# voltage_sensor_v0_4.net
KiCad netlist of a schematic drawn in EAGLE
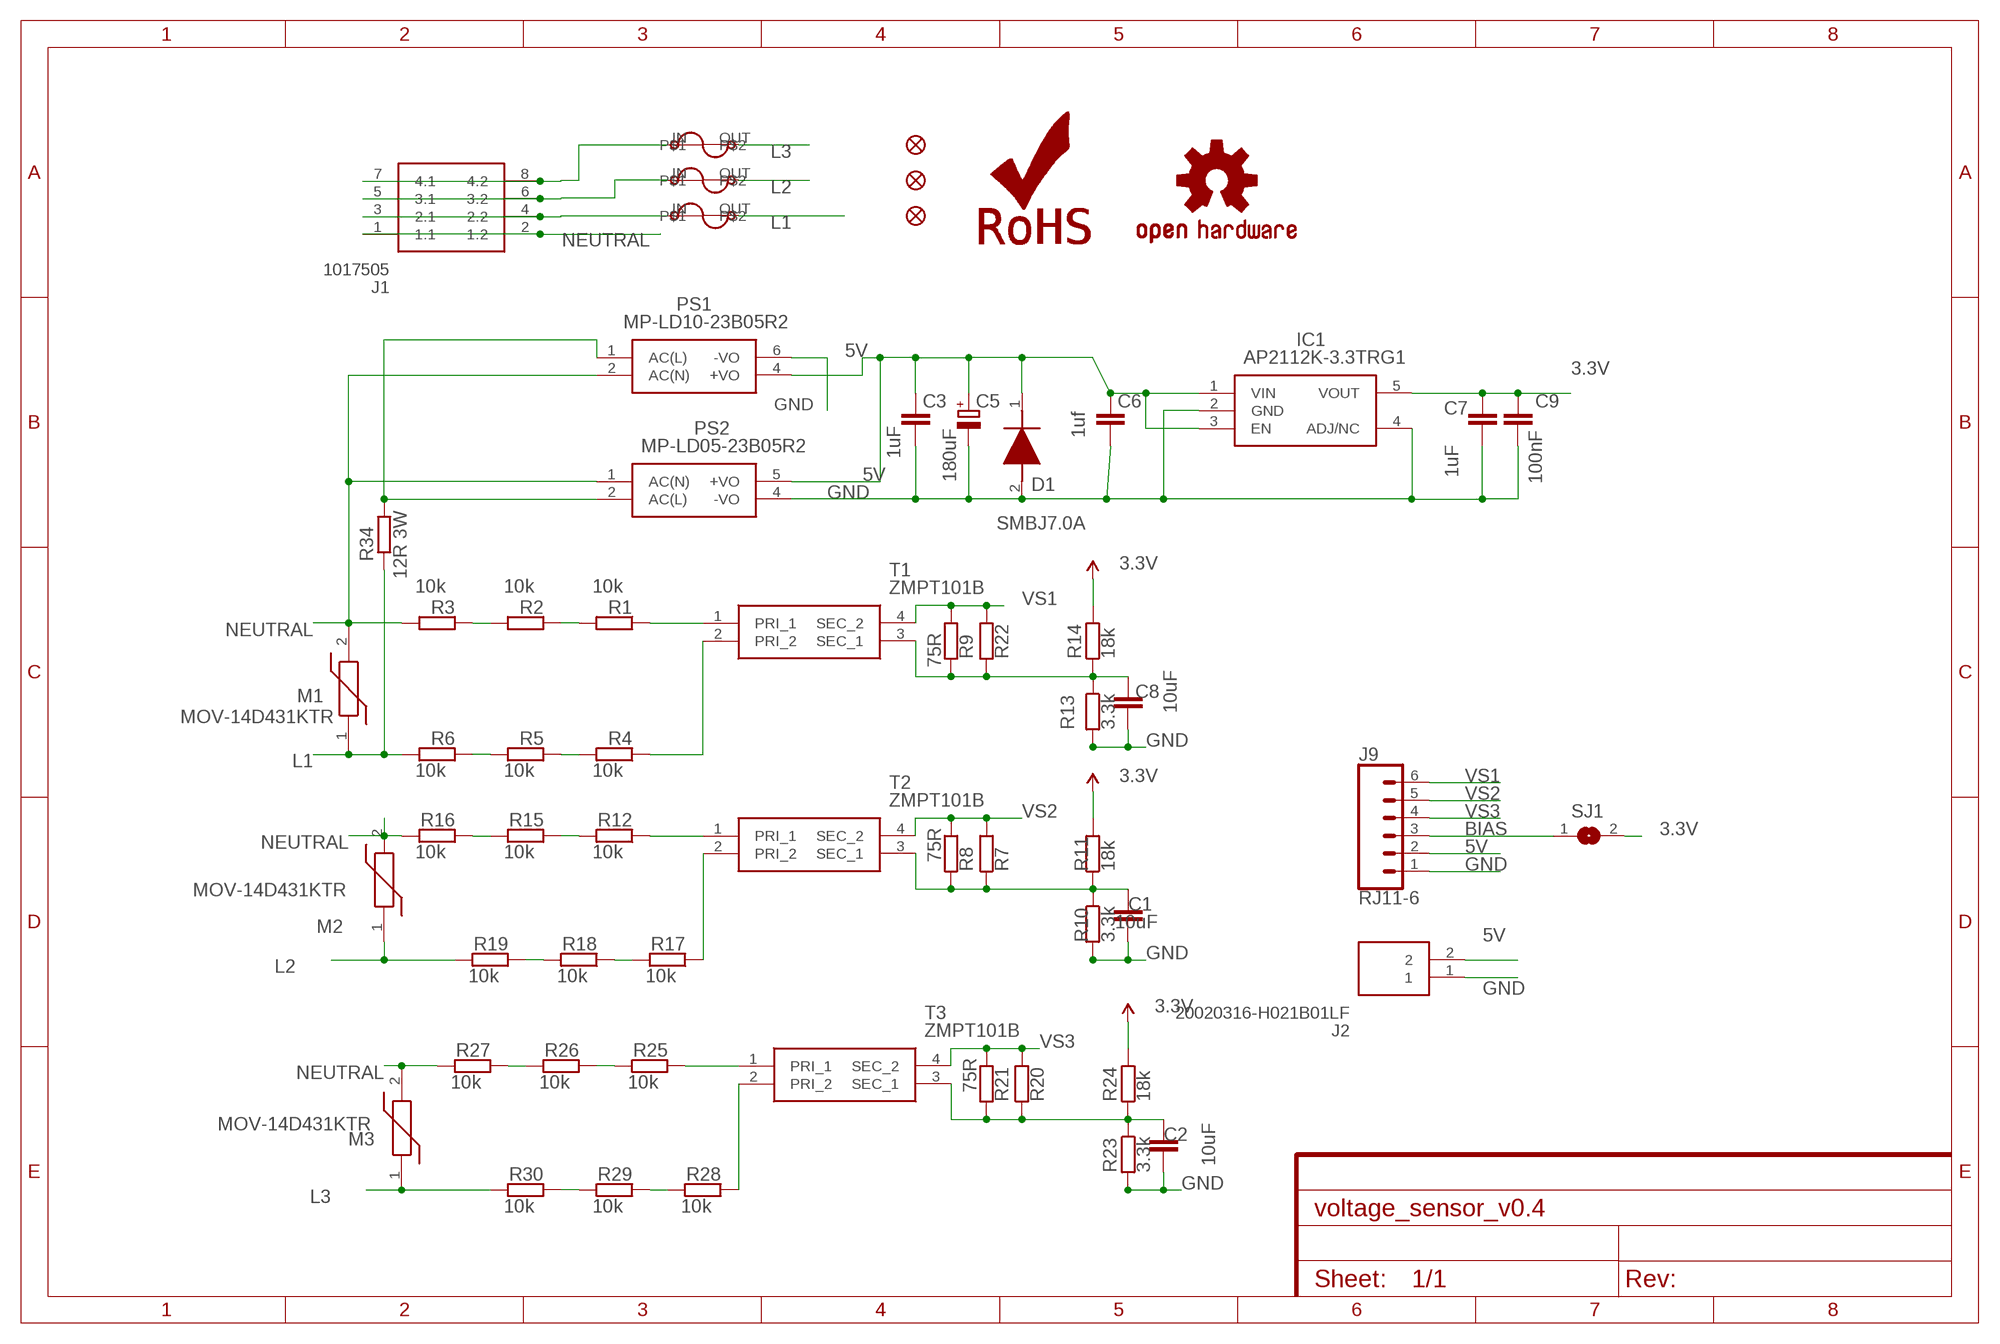
[diagram p0: schematic, sheet 1]

(export (version "E")
  (design (tool "Eeschema 10.0.6"))
  (components
    (comp (ref "C1")
      (value "10uF")
      (footprint "eagle-import:C0603")
      (libsource (lib "eagle-import") (part "C-EUC0603"))
    )
    (comp (ref "C2")
      (value "10uF")
      (footprint "eagle-import:C0603")
      (libsource (lib "eagle-import") (part "C-EUC0603"))
    )
    (comp (ref "C3")
      (value "1uF")
      (footprint "eagle-import:C0603")
      (libsource (lib "eagle-import") (part "C-EUC0603"))
    )
    (comp (ref "C5")
      (value "180uF")
      (footprint "eagle-import:PANASONIC_C")
      (libsource (lib "eagle-import") (part "CPOL-EUC"))
    )
    (comp (ref "C6")
      (value "1uf")
      (footprint "eagle-import:C0603")
      (libsource (lib "eagle-import") (part "C-EUC0603"))
    )
    (comp (ref "C7")
      (value "1uF")
      (footprint "eagle-import:C0603")
      (libsource (lib "eagle-import") (part "C-EUC0603"))
    )
    (comp (ref "C8")
      (value "10uF")
      (footprint "eagle-import:C0603")
      (libsource (lib "eagle-import") (part "C-EUC0603"))
    )
    (comp (ref "C9")
      (value "100nF")
      (footprint "eagle-import:C0603")
      (libsource (lib "eagle-import") (part "C-EUC0603"))
    )
    (comp (ref "D1")
      (value "SMBJ7.0A")
      (footprint "eagle-import:DIOM5336X244N")
      (libsource (lib "eagle-import") (part "SMBJ7.0A"))
    )
    (comp (ref "F1")
      (value "2A/250V")
      (footprint "eagle-import:BELFUSE1A")
      (libsource (lib "eagle-import") (part "BEL1AFUSE"))
    )
    (comp (ref "F2")
      (value "2A/250V")
      (footprint "eagle-import:BELFUSE1A")
      (libsource (lib "eagle-import") (part "BEL1AFUSE"))
    )
    (comp (ref "F3")
      (value "2A/250V")
      (footprint "eagle-import:BELFUSE1A")
      (libsource (lib "eagle-import") (part "BEL1AFUSE"))
    )
    (comp (ref "FD1")
      (value "FIDUCIAL1X2")
      (footprint "eagle-import:FIDUCIAL-1X2")
      (libsource (lib "eagle-import") (part "FIDUCIAL1X2"))
    )
    (comp (ref "FD2")
      (value "FIDUCIAL1X2")
      (footprint "eagle-import:FIDUCIAL-1X2")
      (libsource (lib "eagle-import") (part "FIDUCIAL1X2"))
    )
    (comp (ref "FD3")
      (value "FIDUCIAL1X2")
      (footprint "eagle-import:FIDUCIAL-1X2")
      (libsource (lib "eagle-import") (part "FIDUCIAL1X2"))
    )
    (comp (ref "IC1")
      (value "AP2112K-3.3TRG1")
      (footprint "eagle-import:SOT95P282X130-5N")
      (fields (field (name "MOUSER_PART_NUMBER") "621-AP2112K-3.3TRG1"))
      (libsource (lib "eagle-import") (part "AP2112K-3.3TRG1"))
    )
    (comp (ref "J1")
      (value "1017505")
      (footprint "eagle-import:1017505")
      (fields (field (name "MOUSER_PART_NUMBER") "651-1017505"))
      (libsource (lib "eagle-import") (part "1017505"))
    )
    (comp (ref "J2")
      (value "20020316-H021B01LF")
      (footprint "eagle-import:20020316H021B01LF")
      (libsource (lib "eagle-import") (part "20020316-H021B01LF"))
    )
    (comp (ref "J9")
      (value "RJ11-6")
      (footprint "eagle-import:RJ11-6")
      (libsource (lib "eagle-import") (part "RJ11-6"))
    )
    (comp (ref "LOGO1")
      (value "ROHS_LOGO")
      (footprint "eagle-import:ROHS_LOGO_0.18_IN")
      (libsource (lib "eagle-import") (part "ROHS_LOGO"))
    )
    (comp (ref "LOGO2")
      (value "OSHW-LOGOS-COPPER")
      (footprint "eagle-import:OSHW-LOGO-S_COPPER")
      (libsource (lib "eagle-import") (part "OSHW-LOGOS-COPPER"))
    )
    (comp (ref "M1")
      (value "MOV-14D431KTR")
      (footprint "eagle-import:MOV14D431KTR")
      (fields (field (name "MOUSER_PART_NUMBER") "652-MOV-14D431KTR"))
      (libsource (lib "eagle-import") (part "MOV-14D431KTR"))
    )
    (comp (ref "M2")
      (value "MOV-14D431KTR")
      (footprint "eagle-import:MOV14D431KTR")
      (fields (field (name "MOUSER_PART_NUMBER") "652-MOV-14D431KTR"))
      (libsource (lib "eagle-import") (part "MOV-14D431KTR"))
    )
    (comp (ref "M3")
      (value "MOV-14D431KTR")
      (footprint "eagle-import:MOV14D431KTR")
      (fields (field (name "MOUSER_PART_NUMBER") "652-MOV-14D431KTR"))
      (libsource (lib "eagle-import") (part "MOV-14D431KTR"))
    )
    (comp (ref "PS1")
      (value "MP-LD10-23B05R2")
      (footprint "eagle-import:MPLD1023B12R2")
      (libsource (lib "eagle-import") (part "MP-LD10-23B12R2"))
    )
    (comp (ref "PS2")
      (value "MP-LD05-23B05R2")
      (footprint "eagle-import:MPLD0523B03R2")
      (fields (field (name "MANUFACTURER_PART_NUMBER") "MP-LD05-23B03R2"))
      (libsource (lib "eagle-import") (part "MP-LD05-23B03R2"))
    )
    (comp (ref "R1")
      (value "10k")
      (footprint "eagle-import:R0603")
      (libsource (lib "eagle-import") (part "R-EU_R0603"))
    )
    (comp (ref "R2")
      (value "10k")
      (footprint "eagle-import:R0603")
      (libsource (lib "eagle-import") (part "R-EU_R0603"))
    )
    (comp (ref "R3")
      (value "10k")
      (footprint "eagle-import:R0603")
      (libsource (lib "eagle-import") (part "R-EU_R0603"))
    )
    (comp (ref "R4")
      (value "10k")
      (footprint "eagle-import:R0603")
      (libsource (lib "eagle-import") (part "R-EU_R0603"))
    )
    (comp (ref "R5")
      (value "10k")
      (footprint "eagle-import:R0603")
      (libsource (lib "eagle-import") (part "R-EU_R0603"))
    )
    (comp (ref "R6")
      (value "10k")
      (footprint "eagle-import:R0603")
      (libsource (lib "eagle-import") (part "R-EU_R0603"))
    )
    (comp (ref "R7")
      (value "R-EU_0204/7")
      (footprint "eagle-import:0204_7")
      (libsource (lib "eagle-import") (part "R-EU_0204/7"))
    )
    (comp (ref "R8")
      (value "75R")
      (footprint "eagle-import:R0603")
      (libsource (lib "eagle-import") (part "R-EU_R0603"))
    )
    (comp (ref "R9")
      (value "75R")
      (footprint "eagle-import:R0603")
      (libsource (lib "eagle-import") (part "R-EU_R0603"))
    )
    (comp (ref "R10")
      (value "3.3k")
      (footprint "eagle-import:R0603")
      (libsource (lib "eagle-import") (part "R-EU_R0603"))
    )
    (comp (ref "R11")
      (value "18k")
      (footprint "eagle-import:R0603")
      (libsource (lib "eagle-import") (part "R-EU_R0603"))
    )
    (comp (ref "R12")
      (value "10k")
      (footprint "eagle-import:R0603")
      (libsource (lib "eagle-import") (part "R-EU_R0603"))
    )
    (comp (ref "R13")
      (value "3.3k")
      (footprint "eagle-import:R0603")
      (libsource (lib "eagle-import") (part "R-EU_R0603"))
    )
    (comp (ref "R14")
      (value "18k")
      (footprint "eagle-import:R0603")
      (libsource (lib "eagle-import") (part "R-EU_R0603"))
    )
    (comp (ref "R15")
      (value "10k")
      (footprint "eagle-import:R0603")
      (libsource (lib "eagle-import") (part "R-EU_R0603"))
    )
    (comp (ref "R16")
      (value "10k")
      (footprint "eagle-import:R0603")
      (libsource (lib "eagle-import") (part "R-EU_R0603"))
    )
    (comp (ref "R17")
      (value "10k")
      (footprint "eagle-import:R0603")
      (libsource (lib "eagle-import") (part "R-EU_R0603"))
    )
    (comp (ref "R18")
      (value "10k")
      (footprint "eagle-import:R0603")
      (libsource (lib "eagle-import") (part "R-EU_R0603"))
    )
    (comp (ref "R19")
      (value "10k")
      (footprint "eagle-import:R0603")
      (libsource (lib "eagle-import") (part "R-EU_R0603"))
    )
    (comp (ref "R20")
      (value "R-EU_0204/7")
      (footprint "eagle-import:0204_7")
      (libsource (lib "eagle-import") (part "R-EU_0204/7"))
    )
    (comp (ref "R21")
      (value "75R")
      (footprint "eagle-import:R0603")
      (libsource (lib "eagle-import") (part "R-EU_R0603"))
    )
    (comp (ref "R22")
      (value "R-EU_0204/7")
      (footprint "eagle-import:0204_7")
      (libsource (lib "eagle-import") (part "R-EU_0204/7"))
    )
    (comp (ref "R23")
      (value "3.3k")
      (footprint "eagle-import:R0603")
      (libsource (lib "eagle-import") (part "R-EU_R0603"))
    )
    (comp (ref "R24")
      (value "18k")
      (footprint "eagle-import:R0603")
      (libsource (lib "eagle-import") (part "R-EU_R0603"))
    )
    (comp (ref "R25")
      (value "10k")
      (footprint "eagle-import:R0603")
      (libsource (lib "eagle-import") (part "R-EU_R0603"))
    )
    (comp (ref "R26")
      (value "10k")
      (footprint "eagle-import:R0603")
      (libsource (lib "eagle-import") (part "R-EU_R0603"))
    )
    (comp (ref "R27")
      (value "10k")
      (footprint "eagle-import:R0603")
      (libsource (lib "eagle-import") (part "R-EU_R0603"))
    )
    (comp (ref "R28")
      (value "10k")
      (footprint "eagle-import:R0603")
      (libsource (lib "eagle-import") (part "R-EU_R0603"))
    )
    (comp (ref "R29")
      (value "10k")
      (footprint "eagle-import:R0603")
      (libsource (lib "eagle-import") (part "R-EU_R0603"))
    )
    (comp (ref "R30")
      (value "10k")
      (footprint "eagle-import:R0603")
      (libsource (lib "eagle-import") (part "R-EU_R0603"))
    )
    (comp (ref "R34")
      (value "12R 3W")
      (footprint "eagle-import:R2512")
      (libsource (lib "eagle-import") (part "rcl_334_R-EU_R2512"))
    )
    (comp (ref "SJ1") (value "SJ") (footprint "eagle-import:SJ") (libsource (lib "eagle-import") (part "SJ")))
    (comp (ref "T1")
      (value "ZMPT101B")
      (footprint "eagle-import:ZMPT101B")
      (libsource (lib "eagle-import") (part "ZMPT101B"))
    )
    (comp (ref "T2")
      (value "ZMPT101B")
      (footprint "eagle-import:ZMPT101B")
      (libsource (lib "eagle-import") (part "ZMPT101B"))
    )
    (comp (ref "T3")
      (value "ZMPT101B")
      (footprint "eagle-import:ZMPT101B")
      (libsource (lib "eagle-import") (part "ZMPT101B"))
    )
  )
  (nets
    (net (code "1") (name "/5V") (class "Default")
      (node (ref "C3") (pin "1") (pinfunction "1_1") (pintype "passive"))
      (node (ref "C5") (pin "+") (pinfunction "+_+") (pintype "passive"))
      (node (ref "C6") (pin "1") (pinfunction "1_1") (pintype "passive"))
      (node (ref "D1") (pin "1") (pinfunction "K_1") (pintype "bidirectional"))
      (node (ref "IC1") (pin "1") (pinfunction "VIN_1") (pintype "bidirectional"))
      (node (ref "IC1") (pin "3") (pinfunction "EN_3") (pintype "bidirectional"))
      (node (ref "J2") (pin "2") (pinfunction "2_2") (pintype "bidirectional"))
      (node (ref "J9") (pin "2") (pinfunction "2_2") (pintype "passive"))
      (node (ref "PS1") (pin "4") (pinfunction "+VO_4") (pintype "bidirectional"))
      (node (ref "PS2") (pin "5") (pinfunction "+VO_5") (pintype "bidirectional"))
    )
    (net (code "2") (name "/BIAS") (class "Default")
      (node (ref "J9") (pin "3") (pinfunction "3_3") (pintype "passive"))
      (node (ref "SJ1") (pin "1") (pinfunction "1_1") (pintype "passive"))
    )
    (net (code "3") (name "/GND") (class "Default")
      (node (ref "C1") (pin "2") (pinfunction "2_2") (pintype "passive"))
      (node (ref "C2") (pin "2") (pinfunction "2_2") (pintype "passive"))
      (node (ref "C3") (pin "2") (pinfunction "2_2") (pintype "passive"))
      (node (ref "C5") (pin "-") (pinfunction "-_-") (pintype "passive"))
      (node (ref "C6") (pin "2") (pinfunction "2_2") (pintype "passive"))
      (node (ref "C7") (pin "2") (pinfunction "2_2") (pintype "passive"))
      (node (ref "C8") (pin "2") (pinfunction "2_2") (pintype "passive"))
      (node (ref "C9") (pin "2") (pinfunction "2_2") (pintype "passive"))
      (node (ref "D1") (pin "2") (pinfunction "A_2") (pintype "bidirectional"))
      (node (ref "IC1") (pin "2") (pinfunction "GND_2") (pintype "bidirectional"))
      (node (ref "IC1") (pin "4") (pinfunction "ADJ/NC_4") (pintype "bidirectional"))
      (node (ref "J2") (pin "1") (pinfunction "1_1") (pintype "bidirectional"))
      (node (ref "J9") (pin "1") (pinfunction "1_1") (pintype "passive"))
      (node (ref "PS1") (pin "6") (pinfunction "-VO_6") (pintype "bidirectional"))
      (node (ref "PS2") (pin "4") (pinfunction "-VO_4") (pintype "bidirectional"))
      (node (ref "R10") (pin "2") (pinfunction "2_2") (pintype "passive"))
      (node (ref "R13") (pin "2") (pinfunction "2_2") (pintype "passive"))
      (node (ref "R23") (pin "2") (pinfunction "2_2") (pintype "passive"))
    )
    (net (code "4") (name "/L1") (class "Default")
      (node (ref "F1") (pin "OUT") (pinfunction "P$1_OUT") (pintype "bidirectional"))
      (node (ref "M1") (pin "1") (pinfunction "1_1") (pintype "bidirectional"))
      (node (ref "R34") (pin "1") (pinfunction "1_1") (pintype "passive"))
      (node (ref "R6") (pin "2") (pinfunction "2_2") (pintype "passive"))
    )
    (net (code "5") (name "/L2") (class "Default")
      (node (ref "F2") (pin "OUT") (pinfunction "P$1_OUT") (pintype "bidirectional"))
      (node (ref "M2") (pin "1") (pinfunction "1_1") (pintype "bidirectional"))
      (node (ref "R19") (pin "2") (pinfunction "2_2") (pintype "passive"))
    )
    (net (code "6") (name "/L3") (class "Default")
      (node (ref "F3") (pin "OUT") (pinfunction "P$1_OUT") (pintype "bidirectional"))
      (node (ref "M3") (pin "1") (pinfunction "1_1") (pintype "bidirectional"))
      (node (ref "R30") (pin "2") (pinfunction "2_2") (pintype "passive"))
    )
    (net (code "7") (name "/NEUTRAL") (class "Default")
      (node (ref "J1") (pin "1") (pinfunction "1.1_1") (pintype "bidirectional"))
      (node (ref "J1") (pin "2") (pinfunction "1.2_2") (pintype "bidirectional"))
      (node (ref "M1") (pin "2") (pinfunction "2_2") (pintype "bidirectional"))
      (node (ref "M2") (pin "2") (pinfunction "2_2") (pintype "bidirectional"))
      (node (ref "M3") (pin "2") (pinfunction "2_2") (pintype "bidirectional"))
      (node (ref "PS1") (pin "2") (pinfunction "AC(N)_2") (pintype "bidirectional"))
      (node (ref "PS2") (pin "1") (pinfunction "AC(N)_1") (pintype "bidirectional"))
      (node (ref "R16") (pin "2") (pinfunction "2_2") (pintype "passive"))
      (node (ref "R27") (pin "2") (pinfunction "2_2") (pintype "passive"))
      (node (ref "R3") (pin "2") (pinfunction "2_2") (pintype "passive"))
    )
    (net (code "8") (name "/VS1") (class "Default")
      (node (ref "J9") (pin "6") (pinfunction "6_6") (pintype "passive"))
      (node (ref "R22") (pin "2") (pinfunction "2_2") (pintype "passive"))
      (node (ref "R9") (pin "2") (pinfunction "2_2") (pintype "passive"))
      (node (ref "T1") (pin "4") (pinfunction "SEC_2_4") (pintype "bidirectional"))
    )
    (net (code "9") (name "/VS2") (class "Default")
      (node (ref "J9") (pin "5") (pinfunction "5_5") (pintype "passive"))
      (node (ref "R7") (pin "2") (pinfunction "2_2") (pintype "passive"))
      (node (ref "R8") (pin "2") (pinfunction "2_2") (pintype "passive"))
      (node (ref "T2") (pin "4") (pinfunction "SEC_2_4") (pintype "bidirectional"))
    )
    (net (code "10") (name "/VS3") (class "Default")
      (node (ref "J9") (pin "4") (pinfunction "4_4") (pintype "passive"))
      (node (ref "R20") (pin "2") (pinfunction "2_2") (pintype "passive"))
      (node (ref "R21") (pin "2") (pinfunction "2_2") (pintype "passive"))
      (node (ref "T3") (pin "4") (pinfunction "SEC_2_4") (pintype "bidirectional"))
    )
    (net (code "11") (name "3.3V") (class "Default")
      (node (ref "C7") (pin "1") (pinfunction "1_1") (pintype "passive"))
      (node (ref "C9") (pin "1") (pinfunction "1_1") (pintype "passive"))
      (node (ref "IC1") (pin "5") (pinfunction "VOUT_5") (pintype "bidirectional"))
      (node (ref "R11") (pin "2") (pinfunction "2_2") (pintype "passive"))
      (node (ref "R14") (pin "2") (pinfunction "2_2") (pintype "passive"))
      (node (ref "R24") (pin "2") (pinfunction "2_2") (pintype "passive"))
      (node (ref "SJ1") (pin "2") (pinfunction "2_2") (pintype "passive"))
    )
    (net (code "12") (name "Net-(F1-P$2)") (class "Default")
      (node (ref "F1") (pin "IN") (pinfunction "P$2_IN") (pintype "bidirectional"))
      (node (ref "J1") (pin "3") (pinfunction "2.1_3") (pintype "bidirectional"))
      (node (ref "J1") (pin "4") (pinfunction "2.2_4") (pintype "bidirectional"))
    )
    (net (code "13") (name "Net-(F2-P$2)") (class "Default")
      (node (ref "F2") (pin "IN") (pinfunction "P$2_IN") (pintype "bidirectional"))
      (node (ref "J1") (pin "5") (pinfunction "3.1_5") (pintype "bidirectional"))
      (node (ref "J1") (pin "6") (pinfunction "3.2_6") (pintype "bidirectional"))
    )
    (net (code "14") (name "Net-(F3-P$2)") (class "Default")
      (node (ref "F3") (pin "IN") (pinfunction "P$2_IN") (pintype "bidirectional"))
      (node (ref "J1") (pin "7") (pinfunction "4.1_7") (pintype "bidirectional"))
      (node (ref "J1") (pin "8") (pinfunction "4.2_8") (pintype "bidirectional"))
    )
    (net (code "15") (name "Net-(PS1-AC(L))") (class "Default")
      (node (ref "PS1") (pin "1") (pinfunction "AC(L)_1") (pintype "bidirectional"))
      (node (ref "PS2") (pin "2") (pinfunction "AC(L)_2") (pintype "bidirectional"))
      (node (ref "R34") (pin "2") (pinfunction "2_2") (pintype "passive"))
    )
    (net (code "16") (name "Net-(R1-Pad2)") (class "Default")
      (node (ref "R1") (pin "2") (pinfunction "2_2") (pintype "passive"))
      (node (ref "R2") (pin "1") (pinfunction "1_1") (pintype "passive"))
    )
    (net (code "17") (name "Net-(R2-Pad2)") (class "Default")
      (node (ref "R2") (pin "2") (pinfunction "2_2") (pintype "passive"))
      (node (ref "R3") (pin "1") (pinfunction "1_1") (pintype "passive"))
    )
    (net (code "18") (name "Net-(R4-Pad2)") (class "Default")
      (node (ref "R4") (pin "2") (pinfunction "2_2") (pintype "passive"))
      (node (ref "R5") (pin "1") (pinfunction "1_1") (pintype "passive"))
    )
    (net (code "19") (name "Net-(R5-Pad2)") (class "Default")
      (node (ref "R5") (pin "2") (pinfunction "2_2") (pintype "passive"))
      (node (ref "R6") (pin "1") (pinfunction "1_1") (pintype "passive"))
    )
    (net (code "20") (name "Net-(R12-Pad2)") (class "Default")
      (node (ref "R12") (pin "2") (pinfunction "2_2") (pintype "passive"))
      (node (ref "R15") (pin "1") (pinfunction "1_1") (pintype "passive"))
    )
    (net (code "21") (name "Net-(R15-Pad2)") (class "Default")
      (node (ref "R15") (pin "2") (pinfunction "2_2") (pintype "passive"))
      (node (ref "R16") (pin "1") (pinfunction "1_1") (pintype "passive"))
    )
    (net (code "22") (name "Net-(R17-Pad2)") (class "Default")
      (node (ref "R17") (pin "2") (pinfunction "2_2") (pintype "passive"))
      (node (ref "R18") (pin "1") (pinfunction "1_1") (pintype "passive"))
    )
    (net (code "23") (name "Net-(R18-Pad2)") (class "Default")
      (node (ref "R18") (pin "2") (pinfunction "2_2") (pintype "passive"))
      (node (ref "R19") (pin "1") (pinfunction "1_1") (pintype "passive"))
    )
    (net (code "24") (name "Net-(R25-Pad2)") (class "Default")
      (node (ref "R25") (pin "2") (pinfunction "2_2") (pintype "passive"))
      (node (ref "R26") (pin "1") (pinfunction "1_1") (pintype "passive"))
    )
    (net (code "25") (name "Net-(R26-Pad2)") (class "Default")
      (node (ref "R26") (pin "2") (pinfunction "2_2") (pintype "passive"))
      (node (ref "R27") (pin "1") (pinfunction "1_1") (pintype "passive"))
    )
    (net (code "26") (name "Net-(R28-Pad2)") (class "Default")
      (node (ref "R28") (pin "2") (pinfunction "2_2") (pintype "passive"))
      (node (ref "R29") (pin "1") (pinfunction "1_1") (pintype "passive"))
    )
    (net (code "27") (name "Net-(R29-Pad2)") (class "Default")
      (node (ref "R29") (pin "2") (pinfunction "2_2") (pintype "passive"))
      (node (ref "R30") (pin "1") (pinfunction "1_1") (pintype "passive"))
    )
    (net (code "28") (name "Net-(T1-PRI_1)") (class "Default")
      (node (ref "R1") (pin "1") (pinfunction "1_1") (pintype "passive"))
      (node (ref "T1") (pin "1") (pinfunction "PRI_1_1") (pintype "bidirectional"))
    )
    (net (code "29") (name "Net-(T1-PRI_2)") (class "Default")
      (node (ref "R4") (pin "1") (pinfunction "1_1") (pintype "passive"))
      (node (ref "T1") (pin "2") (pinfunction "PRI_2_2") (pintype "bidirectional"))
    )
    (net (code "30") (name "Net-(T1-SEC_1)") (class "Default")
      (node (ref "C8") (pin "1") (pinfunction "1_1") (pintype "passive"))
      (node (ref "R13") (pin "1") (pinfunction "1_1") (pintype "passive"))
      (node (ref "R14") (pin "1") (pinfunction "1_1") (pintype "passive"))
      (node (ref "R22") (pin "1") (pinfunction "1_1") (pintype "passive"))
      (node (ref "R9") (pin "1") (pinfunction "1_1") (pintype "passive"))
      (node (ref "T1") (pin "3") (pinfunction "SEC_1_3") (pintype "bidirectional"))
    )
    (net (code "31") (name "Net-(T2-PRI_1)") (class "Default")
      (node (ref "R12") (pin "1") (pinfunction "1_1") (pintype "passive"))
      (node (ref "T2") (pin "1") (pinfunction "PRI_1_1") (pintype "bidirectional"))
    )
    (net (code "32") (name "Net-(T2-PRI_2)") (class "Default")
      (node (ref "R17") (pin "1") (pinfunction "1_1") (pintype "passive"))
      (node (ref "T2") (pin "2") (pinfunction "PRI_2_2") (pintype "bidirectional"))
    )
    (net (code "33") (name "Net-(T2-SEC_1)") (class "Default")
      (node (ref "C1") (pin "1") (pinfunction "1_1") (pintype "passive"))
      (node (ref "R10") (pin "1") (pinfunction "1_1") (pintype "passive"))
      (node (ref "R11") (pin "1") (pinfunction "1_1") (pintype "passive"))
      (node (ref "R7") (pin "1") (pinfunction "1_1") (pintype "passive"))
      (node (ref "R8") (pin "1") (pinfunction "1_1") (pintype "passive"))
      (node (ref "T2") (pin "3") (pinfunction "SEC_1_3") (pintype "bidirectional"))
    )
    (net (code "34") (name "Net-(T3-PRI_1)") (class "Default")
      (node (ref "R25") (pin "1") (pinfunction "1_1") (pintype "passive"))
      (node (ref "T3") (pin "1") (pinfunction "PRI_1_1") (pintype "bidirectional"))
    )
    (net (code "35") (name "Net-(T3-PRI_2)") (class "Default")
      (node (ref "R28") (pin "1") (pinfunction "1_1") (pintype "passive"))
      (node (ref "T3") (pin "2") (pinfunction "PRI_2_2") (pintype "bidirectional"))
    )
    (net (code "36") (name "Net-(T3-SEC_1)") (class "Default")
      (node (ref "C2") (pin "1") (pinfunction "1_1") (pintype "passive"))
      (node (ref "R20") (pin "1") (pinfunction "1_1") (pintype "passive"))
      (node (ref "R21") (pin "1") (pinfunction "1_1") (pintype "passive"))
      (node (ref "R23") (pin "1") (pinfunction "1_1") (pintype "passive"))
      (node (ref "R24") (pin "1") (pinfunction "1_1") (pintype "passive"))
      (node (ref "T3") (pin "3") (pinfunction "SEC_1_3") (pintype "bidirectional"))
    )
  )
)
